# low_level_contoller_board2.net
KiCad netlist of a schematic drawn in EAGLE
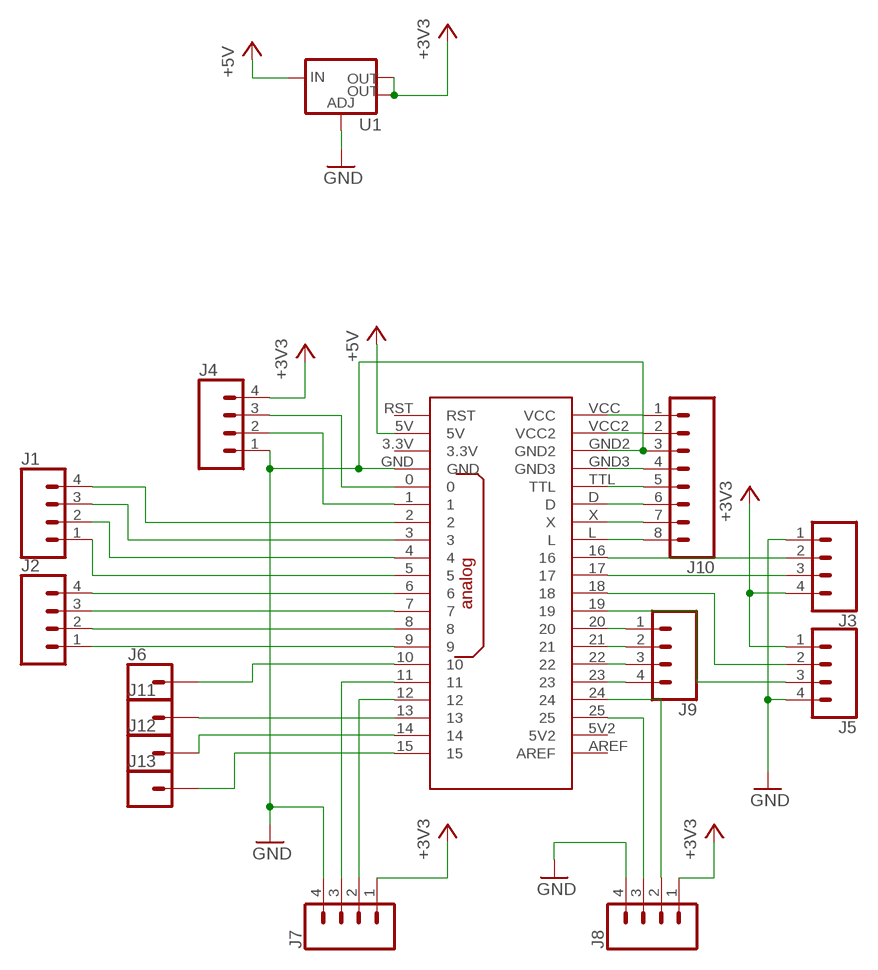
[diagram p0: schematic, sheet 1]

(export (version "E")
  (design (tool "Eeschema 10.0.6"))
  (components
    (comp (ref "J1")
      (value "CONN_04POLAR")
      (footprint "eagle-import:MOLEX-1X4")
      (libsource (lib "eagle-import") (part "CONN_04POLAR"))
    )
    (comp (ref "J2")
      (value "CONN_04POLAR")
      (footprint "eagle-import:MOLEX-1X4")
      (libsource (lib "eagle-import") (part "CONN_04POLAR"))
    )
    (comp (ref "J3")
      (value "CONN_04")
      (footprint "eagle-import:1X04")
      (libsource (lib "eagle-import") (part "CONN_04"))
    )
    (comp (ref "J4")
      (value "CONN_04")
      (footprint "eagle-import:1X04")
      (libsource (lib "eagle-import") (part "CONN_04"))
    )
    (comp (ref "J5")
      (value "CONN_04")
      (footprint "eagle-import:1X04")
      (libsource (lib "eagle-import") (part "CONN_04"))
    )
    (comp (ref "J6")
      (value "CONN_01")
      (footprint "eagle-import:1X01")
      (libsource (lib "eagle-import") (part "CONN_01"))
    )
    (comp (ref "J7")
      (value "CONN_04")
      (footprint "eagle-import:1X04")
      (libsource (lib "eagle-import") (part "CONN_04"))
    )
    (comp (ref "J8")
      (value "CONN_04")
      (footprint "eagle-import:1X04")
      (libsource (lib "eagle-import") (part "CONN_04"))
    )
    (comp (ref "J9")
      (value "CONN_04")
      (footprint "eagle-import:1X04")
      (libsource (lib "eagle-import") (part "CONN_04"))
    )
    (comp (ref "J10")
      (value "CONN_08\"")
      (footprint "eagle-import:1X08")
      (libsource (lib "eagle-import") (part "CONN_08{dblquote}"))
    )
    (comp (ref "J11")
      (value "CONN_01")
      (footprint "eagle-import:1X01")
      (libsource (lib "eagle-import") (part "CONN_01"))
    )
    (comp (ref "J12")
      (value "CONN_01")
      (footprint "eagle-import:1X01")
      (libsource (lib "eagle-import") (part "CONN_01"))
    )
    (comp (ref "J13")
      (value "CONN_01")
      (footprint "eagle-import:1X01")
      (libsource (lib "eagle-import") (part "CONN_01"))
    )
    (comp (ref "U$1")
      (value "OPENCM9.04")
      (footprint "eagle-import:OPENCM9.04")
      (libsource (lib "eagle-import") (part "OPENCM9.04"))
    )
    (comp (ref "U1")
      (value "V_REG_LM1117SOT223")
      (footprint "eagle-import:SOT223")
      (libsource (lib "eagle-import") (part "V_REG_LM1117SOT223"))
    )
  )
  (nets
    (net (code "1") (name "+3V3") (class "Default")
      (node (ref "J3") (pin "4") (pinfunction "4_4") (pintype "passive"))
      (node (ref "J4") (pin "4") (pinfunction "4_4") (pintype "passive"))
      (node (ref "J5") (pin "1") (pinfunction "1_1") (pintype "passive"))
      (node (ref "J7") (pin "1") (pinfunction "1_1") (pintype "passive"))
      (node (ref "J8") (pin "1") (pinfunction "1_1") (pintype "passive"))
      (node (ref "U1") (pin "2") (pinfunction "OUT_2") (pintype "output"))
      (node (ref "U1") (pin "4") (pinfunction "OUT_4") (pintype "output"))
    )
    (net (code "2") (name "+5V") (class "Default")
      (node (ref "U$1") (pin "5V") (pinfunction "5V_5V") (pintype "bidirectional"))
      (node (ref "U1") (pin "3") (pinfunction "IN_3") (pintype "input"))
    )
    (net (code "3") (name "GND") (class "Default")
      (node (ref "J10") (pin "3") (pinfunction "3_3") (pintype "passive"))
      (node (ref "J3") (pin "1") (pinfunction "1_1") (pintype "passive"))
      (node (ref "J4") (pin "1") (pinfunction "1_1") (pintype "passive"))
      (node (ref "J5") (pin "4") (pinfunction "4_4") (pintype "passive"))
      (node (ref "J7") (pin "4") (pinfunction "4_4") (pintype "passive"))
      (node (ref "J8") (pin "4") (pinfunction "4_4") (pintype "passive"))
      (node (ref "U$1") (pin "GND") (pinfunction "GND_GND") (pintype "bidirectional"))
      (node (ref "U$1") (pin "GND2") (pinfunction "GND2_GND2") (pintype "bidirectional"))
      (node (ref "U1") (pin "1") (pinfunction "ADJ_1") (pintype "input"))
    )
    (net (code "4") (name "Net-(J1-Pad1)") (class "Default")
      (node (ref "J1") (pin "1") (pinfunction "1_1") (pintype "passive"))
      (node (ref "U$1") (pin "5") (pinfunction "5_5") (pintype "bidirectional"))
    )
    (net (code "5") (name "Net-(J1-Pad2)") (class "Default")
      (node (ref "J1") (pin "2") (pinfunction "2_2") (pintype "passive"))
      (node (ref "U$1") (pin "4") (pinfunction "4_4") (pintype "bidirectional"))
    )
    (net (code "6") (name "Net-(J1-Pad3)") (class "Default")
      (node (ref "J1") (pin "3") (pinfunction "3_3") (pintype "passive"))
      (node (ref "U$1") (pin "3") (pinfunction "3_3") (pintype "bidirectional"))
    )
    (net (code "7") (name "Net-(J1-Pad4)") (class "Default")
      (node (ref "J1") (pin "4") (pinfunction "4_4") (pintype "passive"))
      (node (ref "U$1") (pin "2") (pinfunction "2_2") (pintype "bidirectional"))
    )
    (net (code "8") (name "Net-(J2-Pad1)") (class "Default")
      (node (ref "J2") (pin "1") (pinfunction "1_1") (pintype "passive"))
      (node (ref "U$1") (pin "9") (pinfunction "9_9") (pintype "bidirectional"))
    )
    (net (code "9") (name "Net-(J2-Pad2)") (class "Default")
      (node (ref "J2") (pin "2") (pinfunction "2_2") (pintype "passive"))
      (node (ref "U$1") (pin "8") (pinfunction "8_8") (pintype "bidirectional"))
    )
    (net (code "10") (name "Net-(J2-Pad3)") (class "Default")
      (node (ref "J2") (pin "3") (pinfunction "3_3") (pintype "passive"))
      (node (ref "U$1") (pin "7") (pinfunction "7_7") (pintype "bidirectional"))
    )
    (net (code "11") (name "Net-(J2-Pad4)") (class "Default")
      (node (ref "J2") (pin "4") (pinfunction "4_4") (pintype "passive"))
      (node (ref "U$1") (pin "6") (pinfunction "6_6") (pintype "bidirectional"))
    )
    (net (code "12") (name "Net-(J3-Pad2)") (class "Default")
      (node (ref "J3") (pin "2") (pinfunction "2_2") (pintype "passive"))
      (node (ref "U$1") (pin "16") (pinfunction "16_16") (pintype "bidirectional"))
    )
    (net (code "13") (name "Net-(J3-Pad3)") (class "Default")
      (node (ref "J3") (pin "3") (pinfunction "3_3") (pintype "passive"))
      (node (ref "U$1") (pin "17") (pinfunction "17_17") (pintype "bidirectional"))
    )
    (net (code "14") (name "Net-(J4-Pad2)") (class "Default")
      (node (ref "J4") (pin "2") (pinfunction "2_2") (pintype "passive"))
      (node (ref "U$1") (pin "1") (pinfunction "1_1") (pintype "bidirectional"))
    )
    (net (code "15") (name "Net-(J4-Pad3)") (class "Default")
      (node (ref "J4") (pin "3") (pinfunction "3_3") (pintype "passive"))
      (node (ref "U$1") (pin "0") (pinfunction "0_0") (pintype "bidirectional"))
    )
    (net (code "16") (name "Net-(J5-Pad2)") (class "Default")
      (node (ref "J5") (pin "2") (pinfunction "2_2") (pintype "passive"))
      (node (ref "U$1") (pin "18") (pinfunction "18_18") (pintype "bidirectional"))
    )
    (net (code "17") (name "Net-(J5-Pad3)") (class "Default")
      (node (ref "J5") (pin "3") (pinfunction "3_3") (pintype "passive"))
      (node (ref "U$1") (pin "19") (pinfunction "19_19") (pintype "bidirectional"))
    )
    (net (code "18") (name "Net-(J6-Pad1)") (class "Default")
      (node (ref "J6") (pin "1") (pinfunction "1_1") (pintype "passive"))
      (node (ref "U$1") (pin "10") (pinfunction "10_10") (pintype "bidirectional"))
    )
    (net (code "19") (name "Net-(J7-Pad2)") (class "Default")
      (node (ref "J7") (pin "2") (pinfunction "2_2") (pintype "passive"))
      (node (ref "U$1") (pin "12") (pinfunction "12_12") (pintype "bidirectional"))
    )
    (net (code "20") (name "Net-(J7-Pad3)") (class "Default")
      (node (ref "J7") (pin "3") (pinfunction "3_3") (pintype "passive"))
      (node (ref "U$1") (pin "11") (pinfunction "11_11") (pintype "bidirectional"))
    )
    (net (code "21") (name "Net-(J8-Pad2)") (class "Default")
      (node (ref "J8") (pin "2") (pinfunction "2_2") (pintype "passive"))
      (node (ref "U$1") (pin "24") (pinfunction "24_24") (pintype "bidirectional"))
    )
    (net (code "22") (name "Net-(J8-Pad3)") (class "Default")
      (node (ref "J8") (pin "3") (pinfunction "3_3") (pintype "passive"))
      (node (ref "U$1") (pin "25") (pinfunction "25_25") (pintype "bidirectional"))
    )
    (net (code "23") (name "Net-(J9-Pad1)") (class "Default")
      (node (ref "J9") (pin "1") (pinfunction "1_1") (pintype "passive"))
      (node (ref "U$1") (pin "20") (pinfunction "20_20") (pintype "bidirectional"))
    )
    (net (code "24") (name "Net-(J9-Pad2)") (class "Default")
      (node (ref "J9") (pin "2") (pinfunction "2_2") (pintype "passive"))
      (node (ref "U$1") (pin "21") (pinfunction "21_21") (pintype "bidirectional"))
    )
    (net (code "25") (name "Net-(J9-Pad3)") (class "Default")
      (node (ref "J9") (pin "3") (pinfunction "3_3") (pintype "passive"))
      (node (ref "U$1") (pin "22") (pinfunction "22_22") (pintype "bidirectional"))
    )
    (net (code "26") (name "Net-(J9-Pad4)") (class "Default")
      (node (ref "J9") (pin "4") (pinfunction "4_4") (pintype "passive"))
      (node (ref "U$1") (pin "23") (pinfunction "23_23") (pintype "bidirectional"))
    )
    (net (code "27") (name "Net-(J10-Pad1)") (class "Default")
      (node (ref "J10") (pin "1") (pinfunction "1_1") (pintype "passive"))
      (node (ref "U$1") (pin "VCC") (pinfunction "VCC_VCC") (pintype "bidirectional"))
    )
    (net (code "28") (name "Net-(J10-Pad2)") (class "Default")
      (node (ref "J10") (pin "2") (pinfunction "2_2") (pintype "passive"))
      (node (ref "U$1") (pin "VCC2") (pinfunction "VCC2_VCC2") (pintype "bidirectional"))
    )
    (net (code "29") (name "Net-(J10-Pad4)") (class "Default")
      (node (ref "J10") (pin "4") (pinfunction "4_4") (pintype "passive"))
      (node (ref "U$1") (pin "GND3") (pinfunction "GND3_GND3") (pintype "bidirectional"))
    )
    (net (code "30") (name "Net-(J10-Pad5)") (class "Default")
      (node (ref "J10") (pin "5") (pinfunction "5_5") (pintype "passive"))
      (node (ref "U$1") (pin "TTL") (pinfunction "TTL_TTL") (pintype "bidirectional"))
    )
    (net (code "31") (name "Net-(J10-Pad6)") (class "Default")
      (node (ref "J10") (pin "6") (pinfunction "6_6") (pintype "passive"))
      (node (ref "U$1") (pin "D") (pinfunction "D_D") (pintype "bidirectional"))
    )
    (net (code "32") (name "Net-(J10-Pad7)") (class "Default")
      (node (ref "J10") (pin "7") (pinfunction "7_7") (pintype "passive"))
      (node (ref "U$1") (pin "X") (pinfunction "X_X") (pintype "bidirectional"))
    )
    (net (code "33") (name "Net-(J10-Pad8)") (class "Default")
      (node (ref "J10") (pin "8") (pinfunction "8_8") (pintype "passive"))
      (node (ref "U$1") (pin "L") (pinfunction "L_L") (pintype "bidirectional"))
    )
    (net (code "34") (name "Net-(J11-Pad1)") (class "Default")
      (node (ref "J11") (pin "1") (pinfunction "1_1") (pintype "passive"))
      (node (ref "U$1") (pin "13") (pinfunction "13_13") (pintype "bidirectional"))
    )
    (net (code "35") (name "Net-(J12-Pad1)") (class "Default")
      (node (ref "J12") (pin "1") (pinfunction "1_1") (pintype "passive"))
      (node (ref "U$1") (pin "14") (pinfunction "14_14") (pintype "bidirectional"))
    )
    (net (code "36") (name "Net-(J13-Pad1)") (class "Default")
      (node (ref "J13") (pin "1") (pinfunction "1_1") (pintype "passive"))
      (node (ref "U$1") (pin "15") (pinfunction "15_15") (pintype "bidirectional"))
    )
    (net (code "37") (name "unconnected-(U$1-Pad3.3V)") (class "Default")
      (node (ref "U$1") (pin "3.3V") (pinfunction "3.3V_3.3V") (pintype "bidirectional"))
    )
    (net (code "38") (name "unconnected-(U$1-Pad5V2)") (class "Default")
      (node (ref "U$1") (pin "5V2") (pinfunction "5V2_5V2") (pintype "bidirectional"))
    )
    (net (code "39") (name "unconnected-(U$1-PadAREF)") (class "Default")
      (node (ref "U$1") (pin "AREF") (pinfunction "AREF_AREF") (pintype "bidirectional"))
    )
    (net (code "40") (name "unconnected-(U$1-PadRST)") (class "Default")
      (node (ref "U$1") (pin "RST") (pinfunction "RST_RST") (pintype "bidirectional"))
    )
  )
)
